# pad2.net
KiCad netlist of a schematic drawn in EAGLE
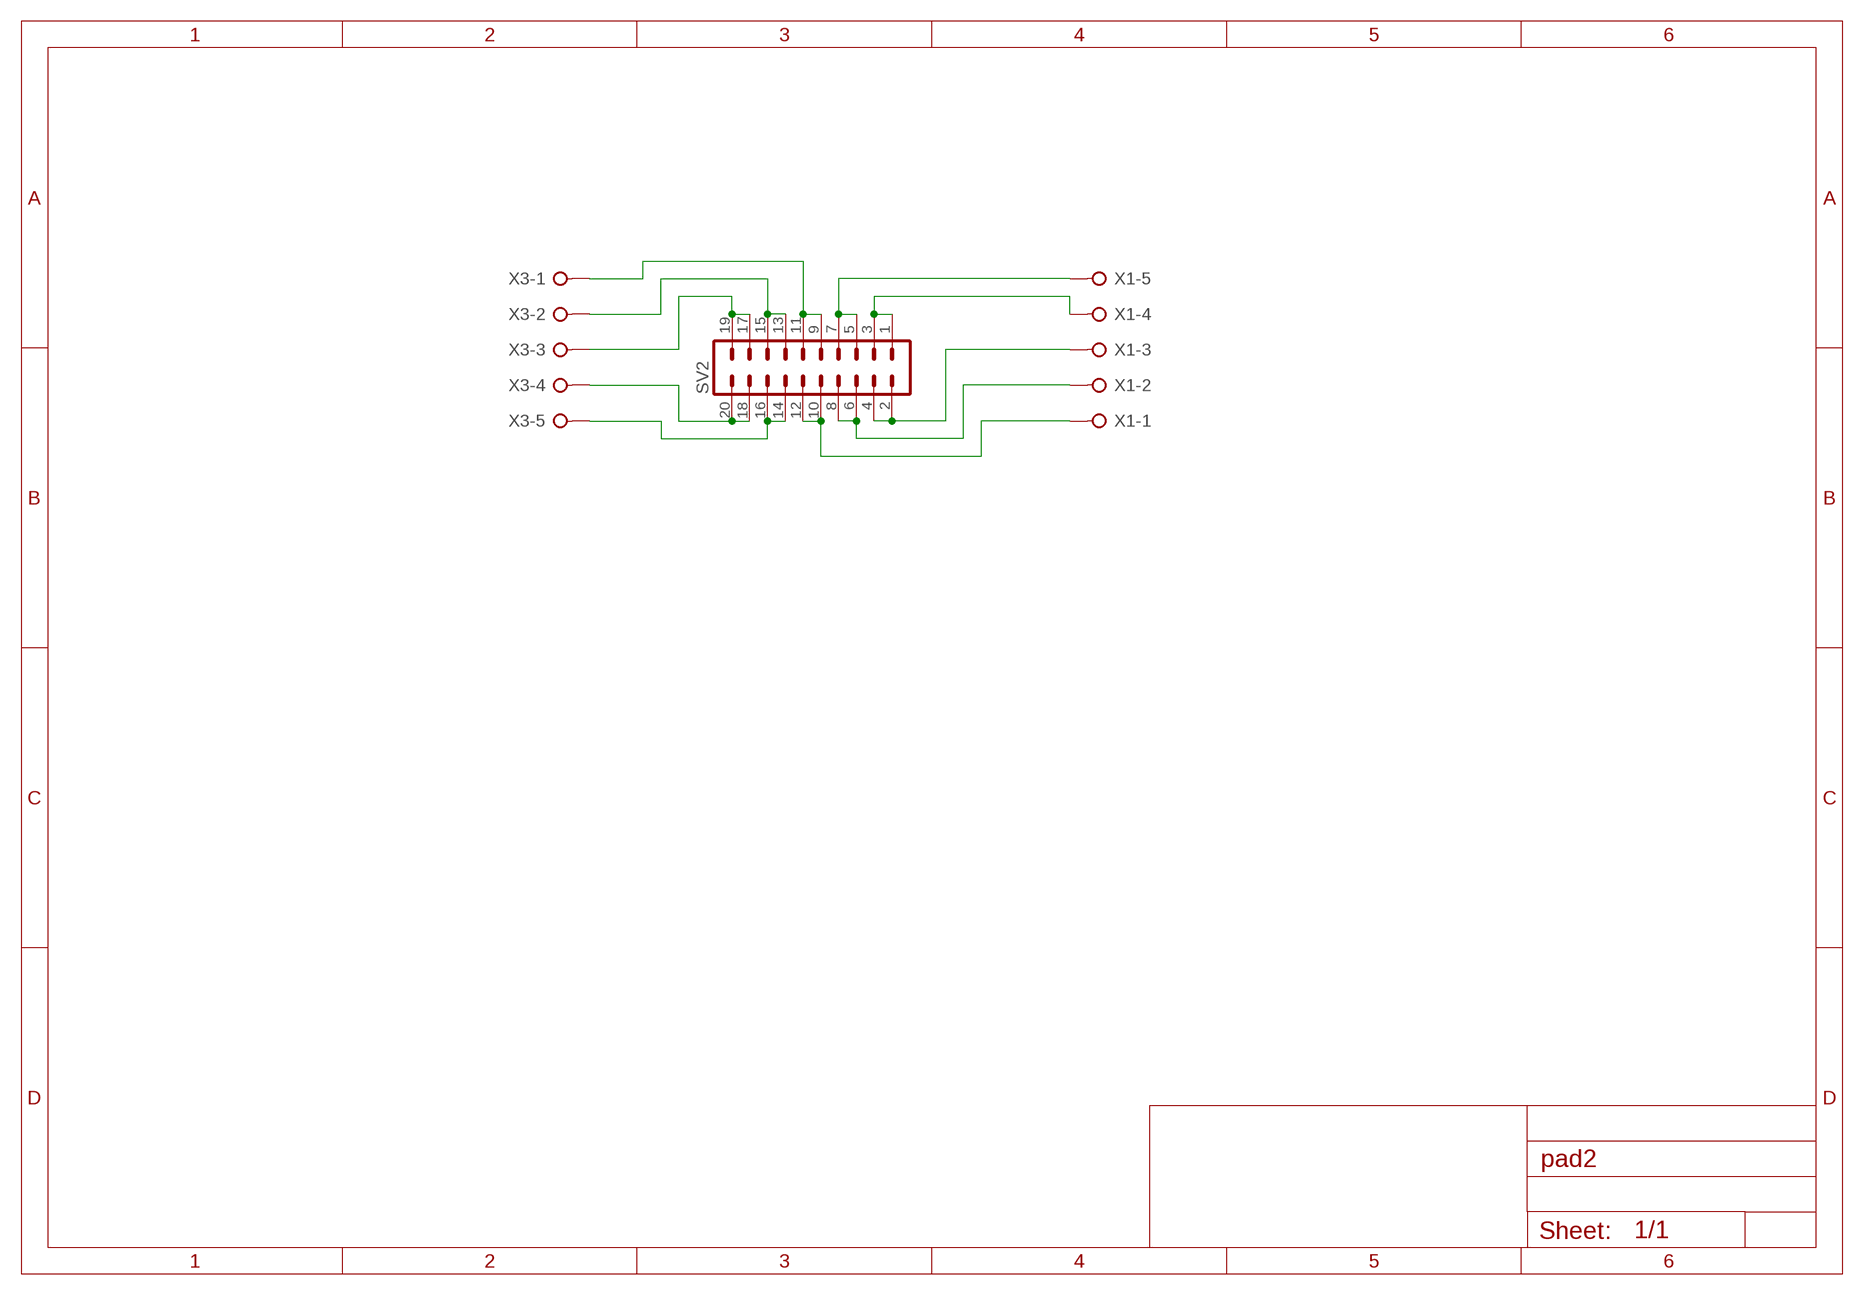
[diagram p0: schematic, sheet 1]

(export (version "E")
  (design (tool "Eeschema 10.0.6"))
  (components
    (comp (ref "SV2")
      (value "MA10-2")
      (footprint "eagle-import:MA10-2")
      (libsource (lib "eagle-import") (part "MA10-2"))
    )
    (comp (ref "X1")
      (value "W237-05P")
      (footprint "eagle-import:W237-5P")
      (libsource (lib "eagle-import") (part "W237-05P"))
    )
    (comp (ref "X3")
      (value "W237-05P")
      (footprint "eagle-import:W237-5P")
      (libsource (lib "eagle-import") (part "W237-05P"))
    )
  )
  (nets
    (net (code "1") (name "Net-(X1A-KL)") (class "Default")
      (node (ref "SV2") (pin "10") (pinfunction "10_10") (pintype "passive"))
      (node (ref "SV2") (pin "12") (pinfunction "12_12") (pintype "passive"))
      (node (ref "X1") (pin "1") (pinfunction "KL_1") (pintype "passive"))
    )
    (net (code "2") (name "Net-(X1B-KL)") (class "Default")
      (node (ref "SV2") (pin "6") (pinfunction "6_6") (pintype "passive"))
      (node (ref "SV2") (pin "8") (pinfunction "8_8") (pintype "passive"))
      (node (ref "X1") (pin "2") (pinfunction "KL_2") (pintype "passive"))
    )
    (net (code "3") (name "Net-(X1C-KL)") (class "Default")
      (node (ref "SV2") (pin "2") (pinfunction "2_2") (pintype "passive"))
      (node (ref "SV2") (pin "4") (pinfunction "4_4") (pintype "passive"))
      (node (ref "X1") (pin "3") (pinfunction "KL_3") (pintype "passive"))
    )
    (net (code "4") (name "Net-(X1D-KL)") (class "Default")
      (node (ref "SV2") (pin "1") (pinfunction "1_1") (pintype "passive"))
      (node (ref "SV2") (pin "3") (pinfunction "3_3") (pintype "passive"))
      (node (ref "X1") (pin "4") (pinfunction "KL_4") (pintype "passive"))
    )
    (net (code "5") (name "Net-(X1E-KL)") (class "Default")
      (node (ref "SV2") (pin "5") (pinfunction "5_5") (pintype "passive"))
      (node (ref "SV2") (pin "7") (pinfunction "7_7") (pintype "passive"))
      (node (ref "X1") (pin "5") (pinfunction "KL_5") (pintype "passive"))
    )
    (net (code "6") (name "Net-(X3A-KL)") (class "Default")
      (node (ref "SV2") (pin "11") (pinfunction "11_11") (pintype "passive"))
      (node (ref "SV2") (pin "9") (pinfunction "9_9") (pintype "passive"))
      (node (ref "X3") (pin "1") (pinfunction "KL_1") (pintype "passive"))
    )
    (net (code "7") (name "Net-(X3B-KL)") (class "Default")
      (node (ref "SV2") (pin "13") (pinfunction "13_13") (pintype "passive"))
      (node (ref "SV2") (pin "15") (pinfunction "15_15") (pintype "passive"))
      (node (ref "X3") (pin "2") (pinfunction "KL_2") (pintype "passive"))
    )
    (net (code "8") (name "Net-(X3C-KL)") (class "Default")
      (node (ref "SV2") (pin "17") (pinfunction "17_17") (pintype "passive"))
      (node (ref "SV2") (pin "19") (pinfunction "19_19") (pintype "passive"))
      (node (ref "X3") (pin "3") (pinfunction "KL_3") (pintype "passive"))
    )
    (net (code "9") (name "Net-(X3D-KL)") (class "Default")
      (node (ref "SV2") (pin "18") (pinfunction "18_18") (pintype "passive"))
      (node (ref "SV2") (pin "20") (pinfunction "20_20") (pintype "passive"))
      (node (ref "X3") (pin "4") (pinfunction "KL_4") (pintype "passive"))
    )
    (net (code "10") (name "Net-(X3E-KL)") (class "Default")
      (node (ref "SV2") (pin "14") (pinfunction "14_14") (pintype "passive"))
      (node (ref "SV2") (pin "16") (pinfunction "16_16") (pintype "passive"))
      (node (ref "X3") (pin "5") (pinfunction "KL_5") (pintype "passive"))
    )
  )
)
